# MRCS-Telephone-Connector-V2_0.net
KiCad netlist of a schematic drawn in EAGLE
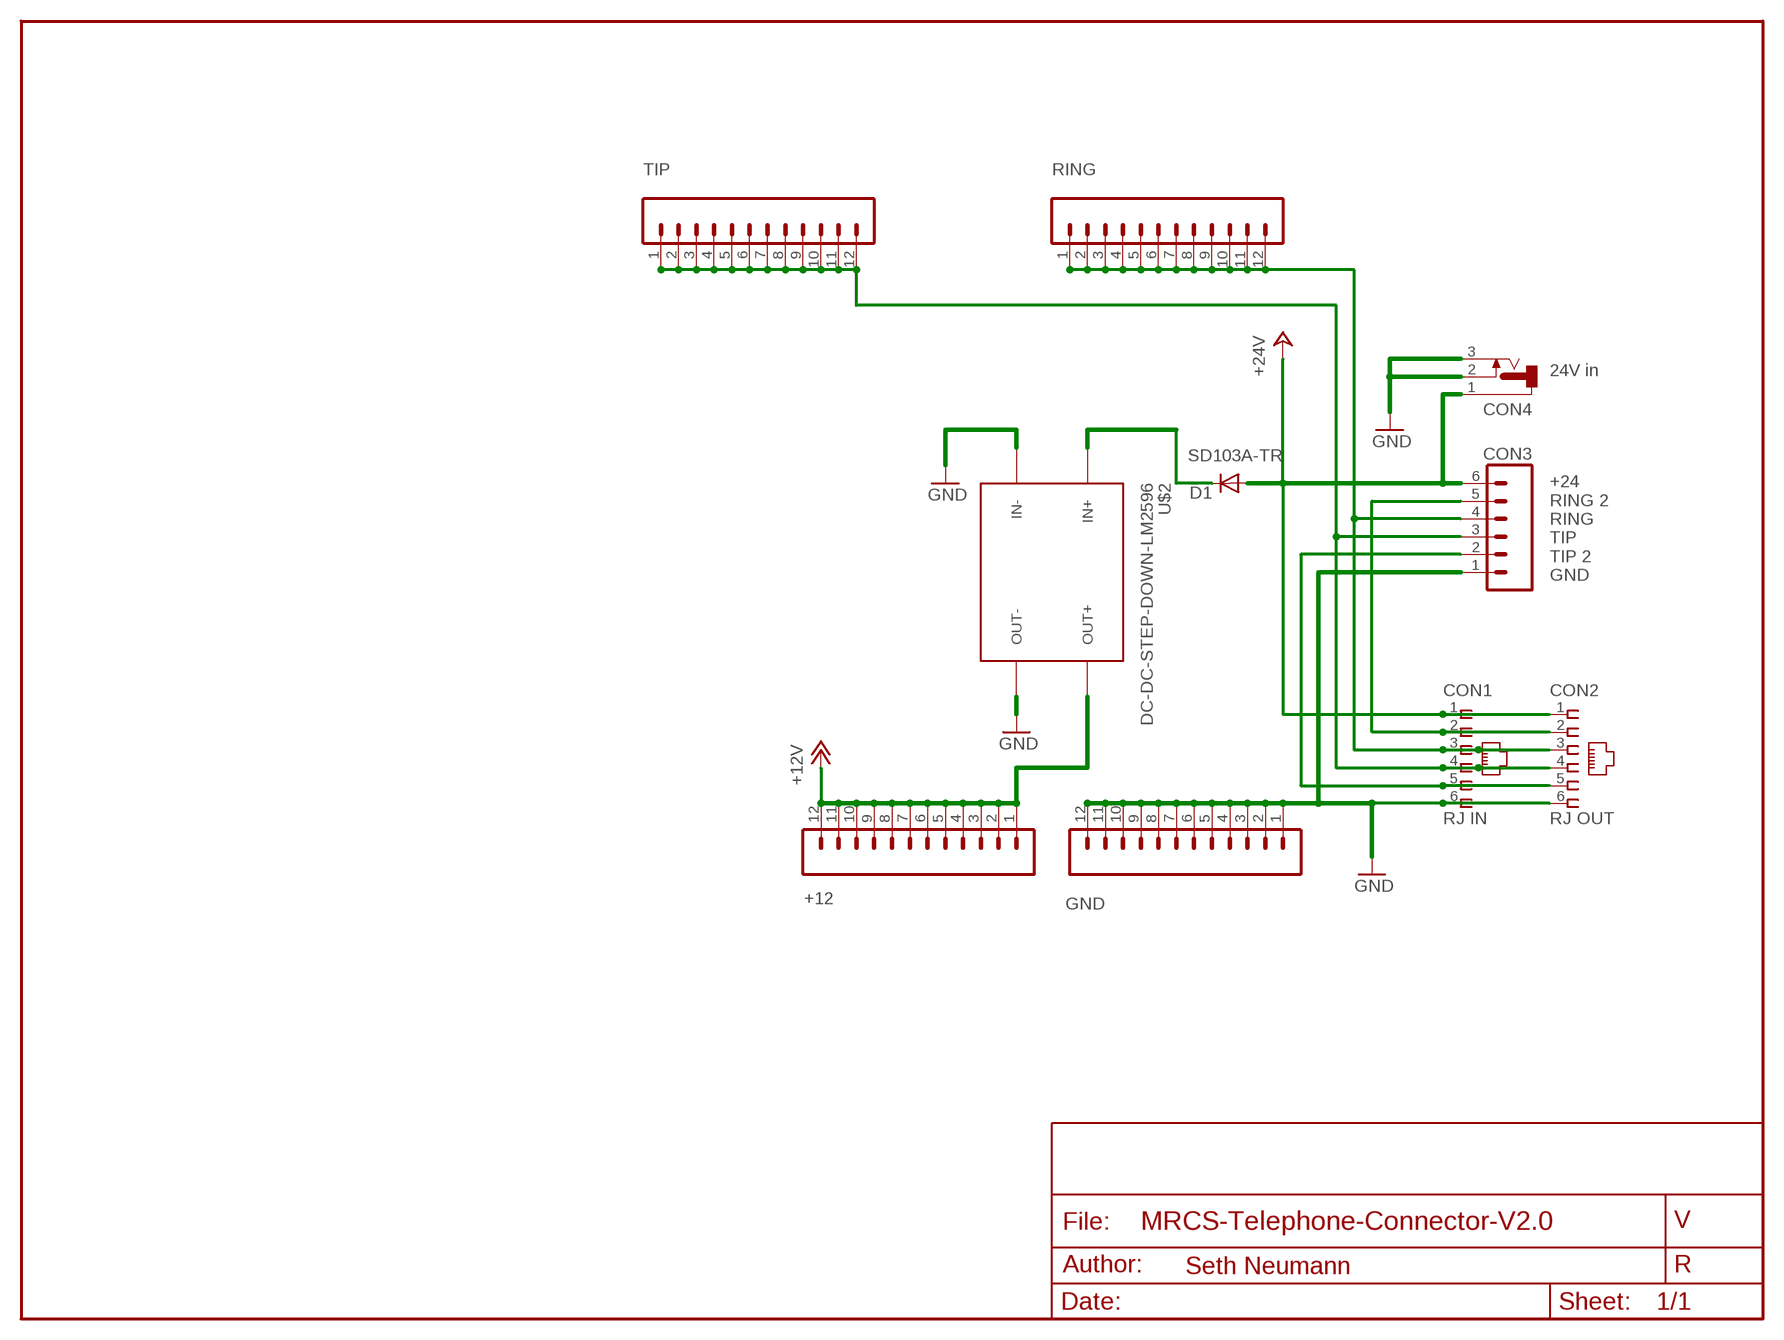
[diagram p0: schematic, sheet 1]

(export (version "E")
  (design (tool "Eeschema 10.0.6"))
  (components
    (comp (ref "+12")
      (value "CONNECTOR-M12LOCK")
      (footprint "eagle-import:1X12_LOCK")
      (libsource (lib "eagle-import") (part "CONNECTOR-M12LOCK"))
    )
    (comp (ref "CON1")
      (value "RJ IN")
      (footprint "eagle-import:RJ25-INVERTED")
      (libsource (lib "eagle-import") (part "CONNECTOR-RJ25-43860-2-MOLEX"))
    )
    (comp (ref "CON2")
      (value "RJ OUT")
      (footprint "eagle-import:RJ25-INVERTED")
      (libsource (lib "eagle-import") (part "CONNECTOR-RJ25-43860-2-MOLEX"))
    )
    (comp (ref "CON3")
      (value "CONNECTOR-M06LOCK")
      (footprint "eagle-import:1X06_LOCK")
      (libsource (lib "eagle-import") (part "CONNECTOR-M06LOCK"))
    )
    (comp (ref "CON4")
      (value "CONNECTOR-DC-POWER-RA")
      (footprint "eagle-import:DCJ0202")
      (libsource (lib "eagle-import") (part "CONNECTOR-DC-POWER-RA"))
    )
    (comp (ref "D1")
      (value "SD103A-TR")
      (footprint "eagle-import:DIODE-1N4001")
      (libsource (lib "eagle-import") (part "DIODEPTH"))
    )
    (comp (ref "GND")
      (value "CONNECTOR-M12LOCK")
      (footprint "eagle-import:1X12_LOCK")
      (libsource (lib "eagle-import") (part "CONNECTOR-M12LOCK"))
    )
    (comp (ref "RING")
      (value "CONNECTOR-M12LOCK")
      (footprint "eagle-import:1X12_LOCK")
      (libsource (lib "eagle-import") (part "CONNECTOR-M12LOCK"))
    )
    (comp (ref "TIP")
      (value "CONNECTOR-M12LOCK")
      (footprint "eagle-import:1X12_LOCK")
      (libsource (lib "eagle-import") (part "CONNECTOR-M12LOCK"))
    )
    (comp (ref "U$2")
      (value "DC-DC-STEP-DOWN-LM2596")
      (footprint "eagle-import:DC-DC-STEP-DOWN-LM2596")
      (libsource (lib "eagle-import") (part "DC-DC-STEP-DOWN-LM2596"))
    )
  )
  (nets
    (net (code "1") (name "+12V") (class "Default")
      (node (ref "+12") (pin "1") (pinfunction "1_1") (pintype "passive"))
      (node (ref "+12") (pin "10") (pinfunction "10_10") (pintype "passive"))
      (node (ref "+12") (pin "11") (pinfunction "11_11") (pintype "passive"))
      (node (ref "+12") (pin "12") (pinfunction "12_12") (pintype "passive"))
      (node (ref "+12") (pin "2") (pinfunction "2_2") (pintype "passive"))
      (node (ref "+12") (pin "3") (pinfunction "3_3") (pintype "passive"))
      (node (ref "+12") (pin "4") (pinfunction "4_4") (pintype "passive"))
      (node (ref "+12") (pin "5") (pinfunction "5_5") (pintype "passive"))
      (node (ref "+12") (pin "6") (pinfunction "6_6") (pintype "passive"))
      (node (ref "+12") (pin "7") (pinfunction "7_7") (pintype "passive"))
      (node (ref "+12") (pin "8") (pinfunction "8_8") (pintype "passive"))
      (node (ref "+12") (pin "9") (pinfunction "9_9") (pintype "passive"))
      (node (ref "U$2") (pin "OUT+") (pinfunction "OUT+_OUT+") (pintype "bidirectional"))
    )
    (net (code "2") (name "+24V") (class "Default")
      (node (ref "CON1") (pin "1") (pinfunction "1_1") (pintype "passive"))
      (node (ref "CON2") (pin "1") (pinfunction "1_1") (pintype "passive"))
      (node (ref "CON3") (pin "6") (pinfunction "6_6") (pintype "passive"))
      (node (ref "CON4") (pin "1") (pinfunction "1_1") (pintype "passive"))
      (node (ref "D1") (pin "A") (pinfunction "A_A") (pintype "passive"))
    )
    (net (code "3") (name "GND") (class "Default")
      (node (ref "CON1") (pin "6") (pinfunction "6_6") (pintype "passive"))
      (node (ref "CON2") (pin "6") (pinfunction "6_6") (pintype "passive"))
      (node (ref "CON3") (pin "1") (pinfunction "1_1") (pintype "passive"))
      (node (ref "CON4") (pin "2") (pinfunction "2_2") (pintype "passive"))
      (node (ref "CON4") (pin "3") (pinfunction "3_3") (pintype "passive"))
      (node (ref "GND") (pin "1") (pinfunction "1_1") (pintype "passive"))
      (node (ref "GND") (pin "10") (pinfunction "10_10") (pintype "passive"))
      (node (ref "GND") (pin "11") (pinfunction "11_11") (pintype "passive"))
      (node (ref "GND") (pin "12") (pinfunction "12_12") (pintype "passive"))
      (node (ref "GND") (pin "2") (pinfunction "2_2") (pintype "passive"))
      (node (ref "GND") (pin "3") (pinfunction "3_3") (pintype "passive"))
      (node (ref "GND") (pin "4") (pinfunction "4_4") (pintype "passive"))
      (node (ref "GND") (pin "5") (pinfunction "5_5") (pintype "passive"))
      (node (ref "GND") (pin "6") (pinfunction "6_6") (pintype "passive"))
      (node (ref "GND") (pin "7") (pinfunction "7_7") (pintype "passive"))
      (node (ref "GND") (pin "8") (pinfunction "8_8") (pintype "passive"))
      (node (ref "GND") (pin "9") (pinfunction "9_9") (pintype "passive"))
      (node (ref "U$2") (pin "IN-") (pinfunction "IN-_IN-") (pintype "bidirectional"))
      (node (ref "U$2") (pin "OUT-") (pinfunction "OUT-_OUT-") (pintype "bidirectional"))
    )
    (net (code "4") (name "Net-(CON1-Pad2)") (class "Default")
      (node (ref "CON1") (pin "2") (pinfunction "2_2") (pintype "passive"))
      (node (ref "CON2") (pin "2") (pinfunction "2_2") (pintype "passive"))
      (node (ref "CON3") (pin "5") (pinfunction "5_5") (pintype "passive"))
    )
    (net (code "5") (name "Net-(CON1-Pad3)") (class "Default")
      (node (ref "CON1") (pin "3") (pinfunction "3_3") (pintype "passive"))
      (node (ref "CON2") (pin "3") (pinfunction "3_3") (pintype "passive"))
      (node (ref "CON3") (pin "4") (pinfunction "4_4") (pintype "passive"))
      (node (ref "RING") (pin "1") (pinfunction "1_1") (pintype "passive"))
      (node (ref "RING") (pin "10") (pinfunction "10_10") (pintype "passive"))
      (node (ref "RING") (pin "11") (pinfunction "11_11") (pintype "passive"))
      (node (ref "RING") (pin "12") (pinfunction "12_12") (pintype "passive"))
      (node (ref "RING") (pin "2") (pinfunction "2_2") (pintype "passive"))
      (node (ref "RING") (pin "3") (pinfunction "3_3") (pintype "passive"))
      (node (ref "RING") (pin "4") (pinfunction "4_4") (pintype "passive"))
      (node (ref "RING") (pin "5") (pinfunction "5_5") (pintype "passive"))
      (node (ref "RING") (pin "6") (pinfunction "6_6") (pintype "passive"))
      (node (ref "RING") (pin "7") (pinfunction "7_7") (pintype "passive"))
      (node (ref "RING") (pin "8") (pinfunction "8_8") (pintype "passive"))
      (node (ref "RING") (pin "9") (pinfunction "9_9") (pintype "passive"))
    )
    (net (code "6") (name "Net-(CON1-Pad4)") (class "Default")
      (node (ref "CON1") (pin "4") (pinfunction "4_4") (pintype "passive"))
      (node (ref "CON2") (pin "4") (pinfunction "4_4") (pintype "passive"))
      (node (ref "CON3") (pin "3") (pinfunction "3_3") (pintype "passive"))
      (node (ref "TIP") (pin "1") (pinfunction "1_1") (pintype "passive"))
      (node (ref "TIP") (pin "10") (pinfunction "10_10") (pintype "passive"))
      (node (ref "TIP") (pin "11") (pinfunction "11_11") (pintype "passive"))
      (node (ref "TIP") (pin "12") (pinfunction "12_12") (pintype "passive"))
      (node (ref "TIP") (pin "2") (pinfunction "2_2") (pintype "passive"))
      (node (ref "TIP") (pin "3") (pinfunction "3_3") (pintype "passive"))
      (node (ref "TIP") (pin "4") (pinfunction "4_4") (pintype "passive"))
      (node (ref "TIP") (pin "5") (pinfunction "5_5") (pintype "passive"))
      (node (ref "TIP") (pin "6") (pinfunction "6_6") (pintype "passive"))
      (node (ref "TIP") (pin "7") (pinfunction "7_7") (pintype "passive"))
      (node (ref "TIP") (pin "8") (pinfunction "8_8") (pintype "passive"))
      (node (ref "TIP") (pin "9") (pinfunction "9_9") (pintype "passive"))
    )
    (net (code "7") (name "Net-(CON1-Pad5)") (class "Default")
      (node (ref "CON1") (pin "5") (pinfunction "5_5") (pintype "passive"))
      (node (ref "CON2") (pin "5") (pinfunction "5_5") (pintype "passive"))
      (node (ref "CON3") (pin "2") (pinfunction "2_2") (pintype "passive"))
    )
    (net (code "8") (name "Net-(D1-PadC)") (class "Default")
      (node (ref "D1") (pin "C") (pinfunction "C_C") (pintype "passive"))
      (node (ref "U$2") (pin "IN+") (pinfunction "IN+_IN+") (pintype "bidirectional"))
    )
  )
)
